# 09_-_Ethernet.net
KiCad netlist of a schematic drawn in Altium Designer
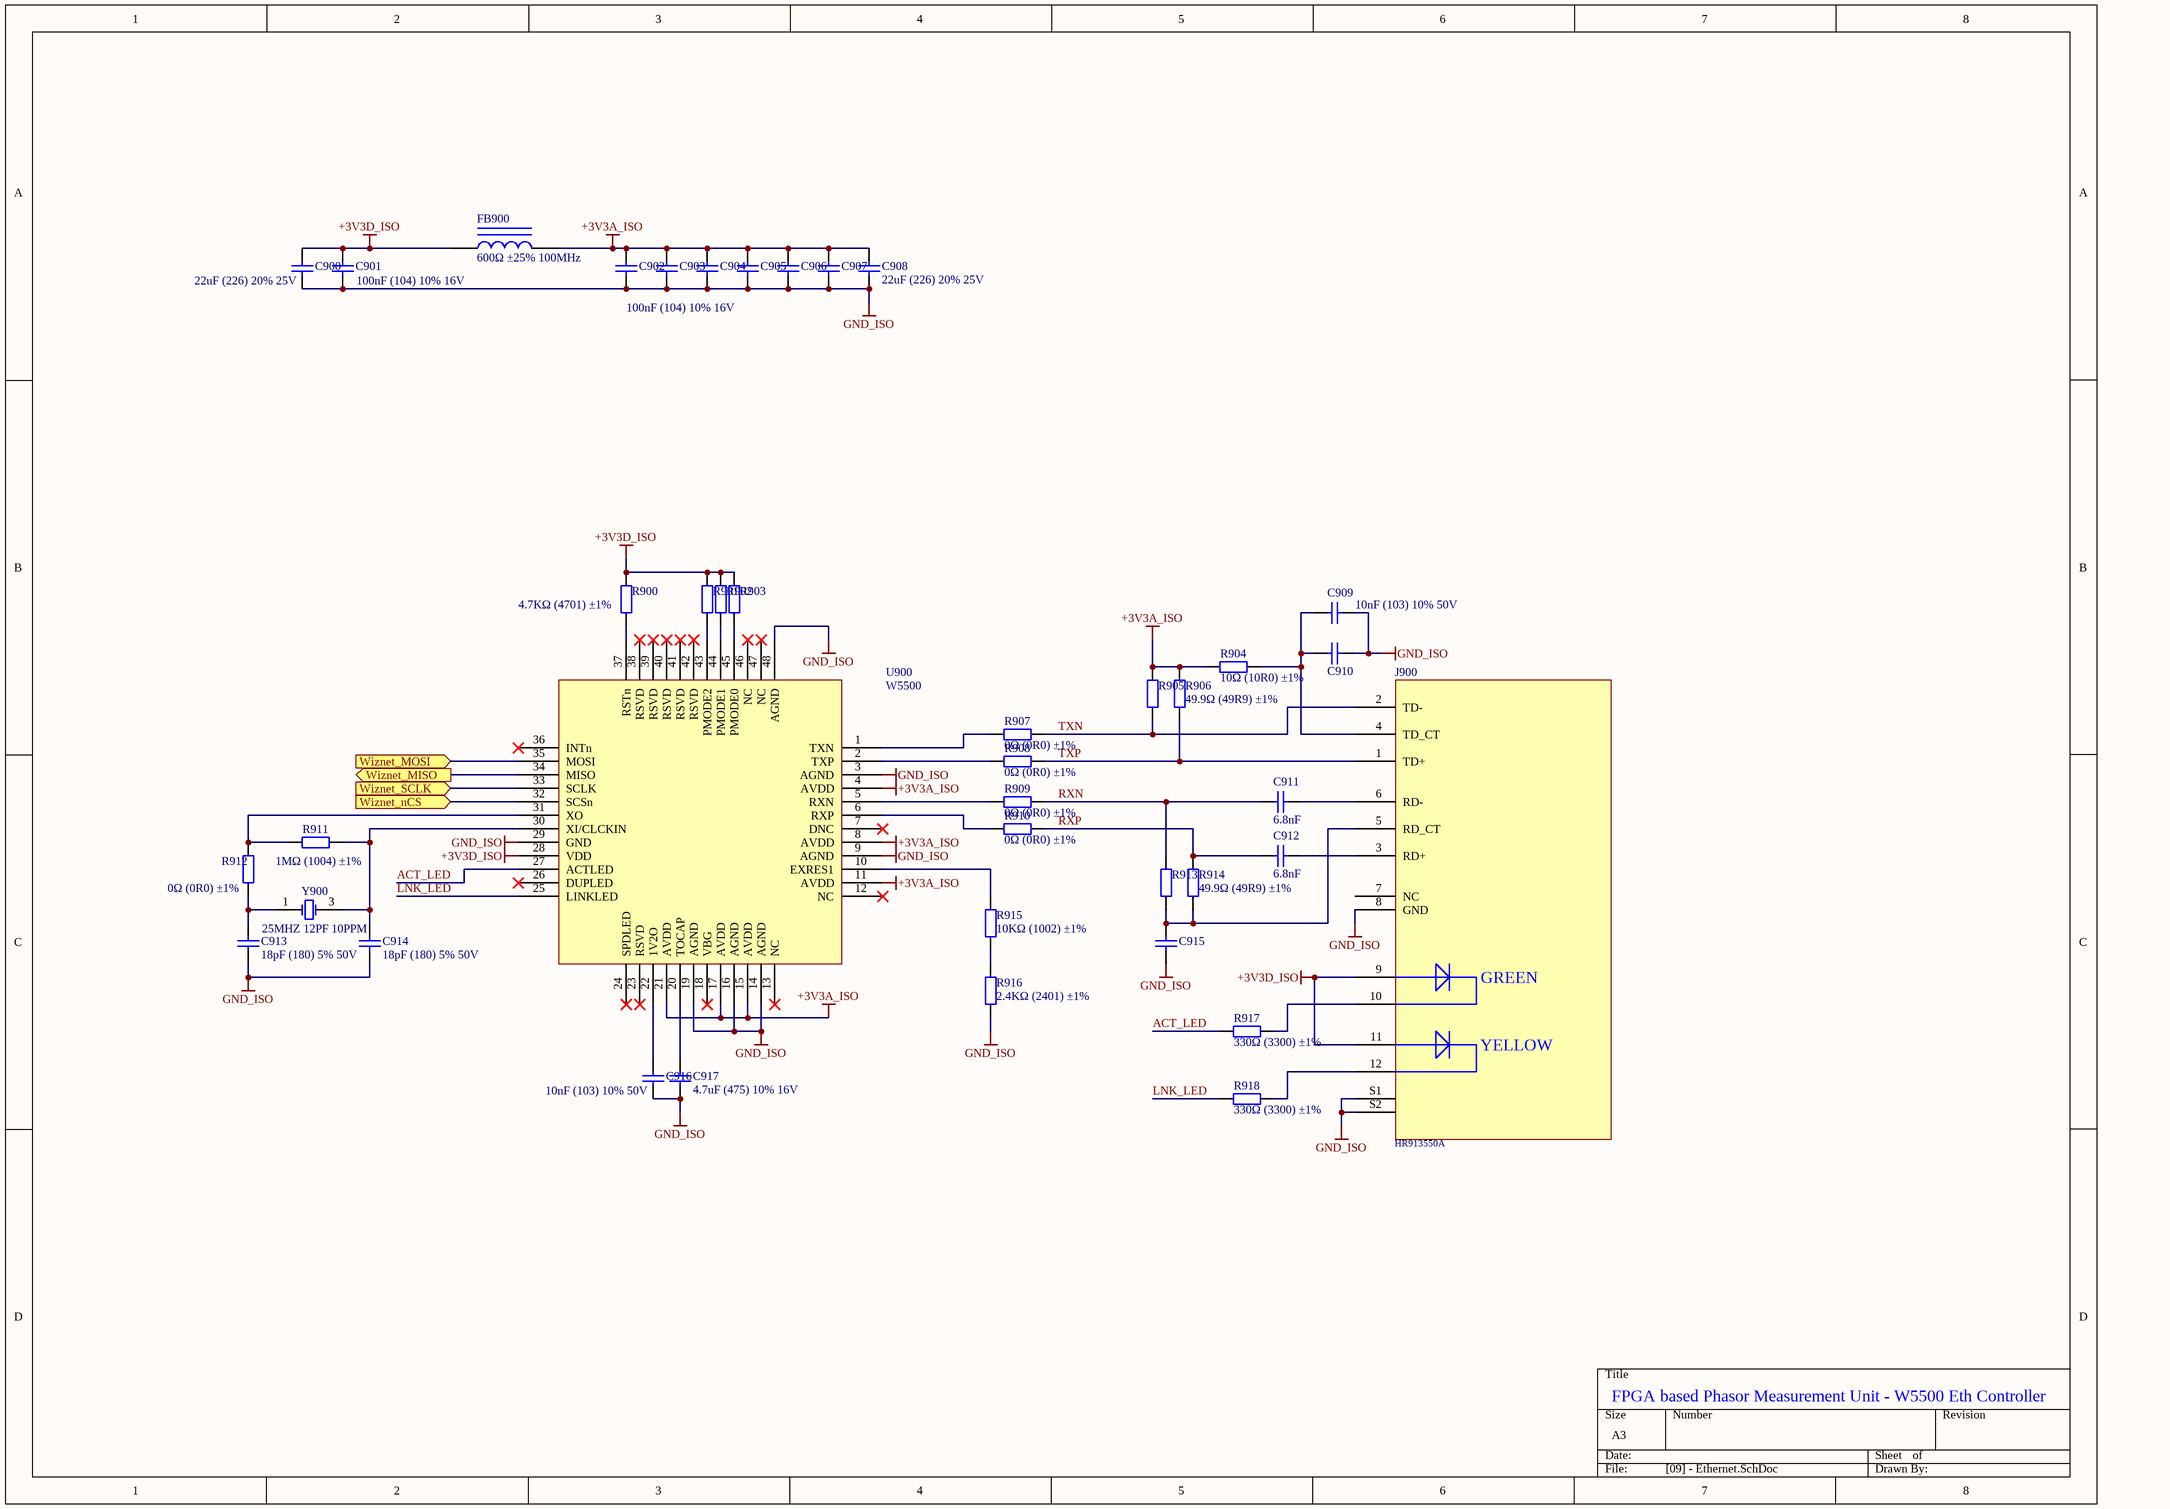
[diagram p0: [09] - Ethernet.SchDoc]

(export (version "E")
  (design (tool "Eeschema 10.0.6"))
  (components
    (comp (ref "C900")
      (value "22uF (226) 20% 25V")
      (footprint "0805_C")
      (description "贴片电容")
      (libsource (lib "Cap") (part "0805 22uF (226) 20% 25V"))
    )
    (comp (ref "C901")
      (value "100nF (104) 10% 16V")
      (footprint "0402_C")
      (description "贴片电容")
      (libsource (lib "Cap") (part "0402 100nF (104) 10% 16V"))
    )
    (comp (ref "C902")
      (value "100nF (104) 10% 16V")
      (footprint "0402_C")
      (description "贴片电容")
      (libsource (lib "Cap") (part "0402 100nF (104) 10% 16V"))
    )
    (comp (ref "C903")
      (value "100nF (104) 10% 16V")
      (footprint "0402_C")
      (description "贴片电容")
      (libsource (lib "Cap") (part "0402 100nF (104) 10% 16V"))
    )
    (comp (ref "C904")
      (value "100nF (104) 10% 16V")
      (footprint "0402_C")
      (description "贴片电容")
      (libsource (lib "Cap") (part "0402 100nF (104) 10% 16V"))
    )
    (comp (ref "C905")
      (value "100nF (104) 10% 16V")
      (footprint "0402_C")
      (description "贴片电容")
      (libsource (lib "Cap") (part "0402 100nF (104) 10% 16V"))
    )
    (comp (ref "C906")
      (value "100nF (104) 10% 16V")
      (footprint "0402_C")
      (description "贴片电容")
      (libsource (lib "Cap") (part "0402 100nF (104) 10% 16V"))
    )
    (comp (ref "C907")
      (value "100nF (104) 10% 16V")
      (footprint "0402_C")
      (description "贴片电容")
      (libsource (lib "Cap") (part "0402 100nF (104) 10% 16V"))
    )
    (comp (ref "C908")
      (value "22uF (226) 20% 25V")
      (footprint "0805_C")
      (description "贴片电容")
      (libsource (lib "Cap") (part "0805 22uF (226) 20% 25V"))
    )
    (comp (ref "C909")
      (value "10nF (103) 10% 50V")
      (footprint "0402_C")
      (description "贴片电容")
      (libsource (lib "Cap") (part "0402 10nF (103) 10% 50V"))
    )
    (comp (ref "C910")
      (value "10nF (103) 10% 50V")
      (footprint "0402_C")
      (description "贴片电容")
      (libsource (lib "Cap") (part "0402 10nF (103) 10% 50V"))
    )
    (comp (ref "C911")
      (value "6.8nF")
      (footprint "0402_C")
      (description "贴片电容")
      (libsource (lib "Cap") (part "0402 6.8nF (682) 10% 50V"))
    )
    (comp (ref "C912")
      (value "6.8nF")
      (footprint "0402_C")
      (description "贴片电容")
      (libsource (lib "Cap") (part "0402 6.8nF (682) 10% 50V"))
    )
    (comp (ref "C913")
      (value "18pF (180) 5% 50V")
      (footprint "0402_C")
      (description "贴片电容")
      (libsource (lib "Cap") (part "0402 18pF (180) 5% 50V"))
    )
    (comp (ref "C914")
      (value "18pF (180) 5% 50V")
      (footprint "0402_C")
      (description "贴片电容")
      (libsource (lib "Cap") (part "0402 18pF (180) 5% 50V"))
    )
    (comp (ref "C915")
      (value "10nF (103) 10% 50V")
      (footprint "0402_C")
      (description "贴片电容")
      (libsource (lib "Cap") (part "0402 10nF (103) 10% 50V"))
    )
    (comp (ref "C916")
      (value "10nF (103) 10% 50V")
      (footprint "0402_C")
      (description "贴片电容")
      (libsource (lib "Cap") (part "0402 10nF (103) 10% 50V"))
    )
    (comp (ref "C917")
      (value "4.7uF (475) 10% 16V")
      (footprint "0603_C")
      (description "贴片电容")
      (libsource (lib "Cap") (part "0603 4.7uF (475) 10% 16V"))
    )
    (comp (ref "FB900")
      (value "600Ω ±25% 100MHz")
      (footprint "0805_L")
      (description "贴片磁珠")
      (libsource (lib "IUD") (part "0805 600Ω 25% 100MHz"))
    )
    (comp (ref "J900")
      (value "HR913550A")
      (footprint "RJ45 MagJack")
      (description "RJ45 12 1 Green - Yellow Through Hole Ethernet Connectors/Modular Connectors (RJ45 RJ11) RoHS")
      (libsource (lib "FPGA_PMU_lib") (part "HR913550A"))
    )
    (comp (ref "R900")
      (value "4.7KΩ (4701) ±1%")
      (footprint "0402_R")
      (description "贴片电阻")
      (libsource (lib "") (part "0402 4.7KΩ (4701) 1%_1"))
    )
    (comp (ref "R901")
      (value "4.7KΩ (4701) ±1%")
      (footprint "0402_R")
      (description "贴片电阻")
      (libsource (lib "RES") (part "0402 4.7KΩ (4701) 1%"))
    )
    (comp (ref "R902")
      (value "4.7KΩ (4701) ±1%")
      (footprint "0402_R")
      (description "贴片电阻")
      (libsource (lib "RES") (part "0402 4.7KΩ (4701) 1%"))
    )
    (comp (ref "R903")
      (value "4.7KΩ (4701) ±1%")
      (footprint "0402_R")
      (description "贴片电阻")
      (libsource (lib "RES") (part "0402 4.7KΩ (4701) 1%"))
    )
    (comp (ref "R904")
      (value "10Ω (10R0) ±1%")
      (footprint "0402_R")
      (description "贴片电阻")
      (libsource (lib "RES") (part "0402 10Ω (10R0) 1%"))
    )
    (comp (ref "R905")
      (value "49.9Ω (49R9) ±1%")
      (footprint "0402_R")
      (description "贴片电阻")
      (libsource (lib "RES") (part "0402 49.9Ω (49R9) 1%"))
    )
    (comp (ref "R906")
      (value "49.9Ω (49R9) ±1%")
      (footprint "0402_R")
      (description "贴片电阻")
      (libsource (lib "RES") (part "0402 49.9Ω (49R9) 1%"))
    )
    (comp (ref "R907")
      (value "0Ω (0R0) ±1%")
      (footprint "0402_R")
      (description "贴片电阻")
      (libsource (lib "") (part "0402 0Ω (0R0) 1%_1"))
    )
    (comp (ref "R908")
      (value "0Ω (0R0) ±1%")
      (footprint "0402_R")
      (description "贴片电阻")
      (libsource (lib "") (part "0402 0Ω (0R0) 1%_1"))
    )
    (comp (ref "R909")
      (value "0Ω (0R0) ±1%")
      (footprint "0402_R")
      (description "贴片电阻")
      (libsource (lib "") (part "0402 0Ω (0R0) 1%_1"))
    )
    (comp (ref "R910")
      (value "0Ω (0R0) ±1%")
      (footprint "0402_R")
      (description "贴片电阻")
      (libsource (lib "") (part "0402 0Ω (0R0) 1%_1"))
    )
    (comp (ref "R911")
      (value "1MΩ (1004) ±1%")
      (footprint "0402_R")
      (description "贴片电阻")
      (libsource (lib "RES") (part "0402 1MΩ (1004) 1%"))
    )
    (comp (ref "R912")
      (value "0Ω (0R0) ±1%")
      (footprint "0402_R")
      (description "贴片电阻")
      (libsource (lib "RES") (part "0402 0Ω (0R0) 1%"))
    )
    (comp (ref "R913")
      (value "49.9Ω (49R9) ±1%")
      (footprint "0402_R")
      (description "贴片电阻")
      (libsource (lib "RES") (part "0402 49.9Ω (49R9) 1%"))
    )
    (comp (ref "R914")
      (value "49.9Ω (49R9) ±1%")
      (footprint "0402_R")
      (description "贴片电阻")
      (libsource (lib "RES") (part "0402 49.9Ω (49R9) 1%"))
    )
    (comp (ref "R915")
      (value "10KΩ (1002) ±1%")
      (footprint "0402_R")
      (description "贴片电阻")
      (libsource (lib "RES") (part "0402 10KΩ (1002) 1%"))
    )
    (comp (ref "R916")
      (value "2.4KΩ (2401) ±1%")
      (footprint "0402_R")
      (description "贴片电阻")
      (libsource (lib "RES") (part "0402 2.4KΩ (2401) 1%"))
    )
    (comp (ref "R917")
      (value "330Ω (3300) ±1%")
      (footprint "0603_R")
      (description "贴片电阻")
      (libsource (lib "RES") (part "0603 330Ω (3300) 1%"))
    )
    (comp (ref "R918")
      (value "330Ω (3300) ±1%")
      (footprint "0603_R")
      (description "贴片电阻")
      (libsource (lib "RES") (part "0603 330Ω (3300) 1%"))
    )
    (comp (ref "U900")
      (value "W5500")
      (footprint "LQFP-48_7x7x05P")
      (description "以太网")
      (libsource (lib "IC") (part "W5500_[C32843]"))
    )
    (comp (ref "Y900")
      (value "25MHZ 12PF 10PPM")
      (footprint "SMD-3225_4P")
      (description "贴片晶振")
      (libsource (lib "CrystalOscillator") (part "SMD-3225_4P  25MHZ 12PF 10PPM"))
    )
  )
  (nets
    (net (code "1") (name "+3V3A_ISO") (class "Default")
      (node (ref "C902") (pin "2") (pinfunction "2_2") (pintype "passive"))
      (node (ref "C903") (pin "2") (pinfunction "2_2") (pintype "passive"))
      (node (ref "C904") (pin "2") (pinfunction "2_2") (pintype "passive"))
      (node (ref "C905") (pin "2") (pinfunction "2_2") (pintype "passive"))
      (node (ref "C906") (pin "2") (pinfunction "2_2") (pintype "passive"))
      (node (ref "C907") (pin "2") (pinfunction "2_2") (pintype "passive"))
      (node (ref "C908") (pin "2") (pinfunction "2_2") (pintype "passive"))
      (node (ref "FB900") (pin "2") (pinfunction "2_2") (pintype "passive"))
      (node (ref "R904") (pin "1") (pinfunction "1_1") (pintype "passive"))
      (node (ref "R905") (pin "2") (pinfunction "2_2") (pintype "passive"))
      (node (ref "R906") (pin "2") (pinfunction "2_2") (pintype "passive"))
      (node (ref "U900") (pin "11") (pinfunction "AVDD_11") (pintype "passive"))
      (node (ref "U900") (pin "15") (pinfunction "AVDD_15") (pintype "passive"))
      (node (ref "U900") (pin "17") (pinfunction "AVDD_17") (pintype "passive"))
      (node (ref "U900") (pin "21") (pinfunction "AVDD_21") (pintype "passive"))
      (node (ref "U900") (pin "4") (pinfunction "AVDD_4") (pintype "passive"))
      (node (ref "U900") (pin "8") (pinfunction "AVDD_8") (pintype "passive"))
    )
    (net (code "2") (name "+3V3D_ISO") (class "Default")
      (node (ref "C900") (pin "2") (pinfunction "2_2") (pintype "passive"))
      (node (ref "C901") (pin "2") (pinfunction "2_2") (pintype "passive"))
      (node (ref "FB900") (pin "1") (pinfunction "1_1") (pintype "passive"))
      (node (ref "J900") (pin "11") (pinfunction "11_11") (pintype "passive"))
      (node (ref "J900") (pin "9") (pinfunction "9_9") (pintype "passive"))
      (node (ref "R900") (pin "1") (pinfunction "1_1") (pintype "passive"))
      (node (ref "R901") (pin "2") (pinfunction "2_2") (pintype "passive"))
      (node (ref "R902") (pin "2") (pinfunction "2_2") (pintype "passive"))
      (node (ref "R903") (pin "2") (pinfunction "2_2") (pintype "passive"))
      (node (ref "U900") (pin "28") (pinfunction "VDD_28") (pintype "passive"))
    )
    (net (code "3") (name "/ACT_LED") (class "Default")
      (node (ref "R917") (pin "1") (pinfunction "1_1") (pintype "passive"))
      (node (ref "U900") (pin "27") (pinfunction "ACTLED_27") (pintype "passive"))
    )
    (net (code "4") (name "/LNK_LED") (class "Default")
      (node (ref "R918") (pin "1") (pinfunction "1_1") (pintype "passive"))
      (node (ref "U900") (pin "25") (pinfunction "LINKLED_25") (pintype "passive"))
    )
    (net (code "5") (name "/RXN") (class "Default")
      (node (ref "C911") (pin "1") (pinfunction "1_1") (pintype "passive"))
      (node (ref "R909") (pin "2") (pinfunction "2_2") (pintype "passive"))
      (node (ref "R913") (pin "2") (pinfunction "2_2") (pintype "passive"))
    )
    (net (code "6") (name "/RXP") (class "Default")
      (node (ref "C912") (pin "1") (pinfunction "1_1") (pintype "passive"))
      (node (ref "R910") (pin "2") (pinfunction "2_2") (pintype "passive"))
      (node (ref "R914") (pin "2") (pinfunction "2_2") (pintype "passive"))
    )
    (net (code "7") (name "/TXN") (class "Default")
      (node (ref "J900") (pin "2") (pinfunction "TD-_2") (pintype "passive"))
      (node (ref "R905") (pin "1") (pinfunction "1_1") (pintype "passive"))
      (node (ref "R907") (pin "2") (pinfunction "2_2") (pintype "passive"))
    )
    (net (code "8") (name "/TXP") (class "Default")
      (node (ref "J900") (pin "1") (pinfunction "TD+_1") (pintype "passive"))
      (node (ref "R906") (pin "1") (pinfunction "1_1") (pintype "passive"))
      (node (ref "R908") (pin "2") (pinfunction "2_2") (pintype "passive"))
    )
    (net (code "9") (name "/Wiznet_MISO") (class "Default")
      (node (ref "U900") (pin "34") (pinfunction "MISO_34") (pintype "passive"))
    )
    (net (code "10") (name "/Wiznet_MOSI") (class "Default")
      (node (ref "U900") (pin "35") (pinfunction "MOSI_35") (pintype "passive"))
    )
    (net (code "11") (name "/Wiznet_SCLK") (class "Default")
      (node (ref "U900") (pin "33") (pinfunction "SCLK_33") (pintype "passive"))
    )
    (net (code "12") (name "/Wiznet_nCS") (class "Default")
      (node (ref "U900") (pin "32") (pinfunction "SCSn_32") (pintype "passive"))
    )
    (net (code "13") (name "GND_ISO") (class "Default")
      (node (ref "C900") (pin "1") (pinfunction "1_1") (pintype "passive"))
      (node (ref "C901") (pin "1") (pinfunction "1_1") (pintype "passive"))
      (node (ref "C902") (pin "1") (pinfunction "1_1") (pintype "passive"))
      (node (ref "C903") (pin "1") (pinfunction "1_1") (pintype "passive"))
      (node (ref "C904") (pin "1") (pinfunction "1_1") (pintype "passive"))
      (node (ref "C905") (pin "1") (pinfunction "1_1") (pintype "passive"))
      (node (ref "C906") (pin "1") (pinfunction "1_1") (pintype "passive"))
      (node (ref "C907") (pin "1") (pinfunction "1_1") (pintype "passive"))
      (node (ref "C908") (pin "1") (pinfunction "1_1") (pintype "passive"))
      (node (ref "C909") (pin "1") (pinfunction "1_1") (pintype "passive"))
      (node (ref "C910") (pin "1") (pinfunction "1_1") (pintype "passive"))
      (node (ref "C913") (pin "1") (pinfunction "1_1") (pintype "passive"))
      (node (ref "C914") (pin "1") (pinfunction "1_1") (pintype "passive"))
      (node (ref "C915") (pin "1") (pinfunction "1_1") (pintype "passive"))
      (node (ref "C916") (pin "1") (pinfunction "1_1") (pintype "passive"))
      (node (ref "C917") (pin "1") (pinfunction "1_1") (pintype "passive"))
      (node (ref "J900") (pin "8") (pinfunction "GND_8") (pintype "passive"))
      (node (ref "J900") (pin "S1") (pinfunction "S1_S1") (pintype "passive"))
      (node (ref "J900") (pin "S2") (pinfunction "S2_S2") (pintype "passive"))
      (node (ref "R916") (pin "1") (pinfunction "1_1") (pintype "passive"))
      (node (ref "U900") (pin "14") (pinfunction "AGND_14") (pintype "passive"))
      (node (ref "U900") (pin "16") (pinfunction "AGND_16") (pintype "passive"))
      (node (ref "U900") (pin "19") (pinfunction "AGND_19") (pintype "passive"))
      (node (ref "U900") (pin "29") (pinfunction "GND_29") (pintype "passive"))
      (node (ref "U900") (pin "3") (pinfunction "AGND_3") (pintype "passive"))
      (node (ref "U900") (pin "48") (pinfunction "AGND_48") (pintype "passive"))
      (node (ref "U900") (pin "9") (pinfunction "AGND_9") (pintype "passive"))
    )
    (net (code "14") (name "Net-(J900-Pad10)") (class "Default")
      (node (ref "J900") (pin "10") (pinfunction "10_10") (pintype "passive"))
      (node (ref "R917") (pin "2") (pinfunction "2_2") (pintype "passive"))
    )
    (net (code "15") (name "Net-(J900-Pad12)") (class "Default")
      (node (ref "J900") (pin "12") (pinfunction "12_12") (pintype "passive"))
      (node (ref "R918") (pin "2") (pinfunction "2_2") (pintype "passive"))
    )
    (net (code "16") (name "Net-(J900-RD+)") (class "Default")
      (node (ref "C912") (pin "2") (pinfunction "2_2") (pintype "passive"))
      (node (ref "J900") (pin "3") (pinfunction "RD+_3") (pintype "passive"))
    )
    (net (code "17") (name "Net-(J900-RD-)") (class "Default")
      (node (ref "C911") (pin "2") (pinfunction "2_2") (pintype "passive"))
      (node (ref "J900") (pin "6") (pinfunction "RD-_6") (pintype "passive"))
    )
    (net (code "18") (name "Net-(J900-RD_CT)") (class "Default")
      (node (ref "C915") (pin "2") (pinfunction "2_2") (pintype "passive"))
      (node (ref "J900") (pin "5") (pinfunction "RD_CT_5") (pintype "passive"))
      (node (ref "R913") (pin "1") (pinfunction "1_1") (pintype "passive"))
      (node (ref "R914") (pin "1") (pinfunction "1_1") (pintype "passive"))
    )
    (net (code "19") (name "Net-(J900-TD_CT)") (class "Default")
      (node (ref "C909") (pin "2") (pinfunction "2_2") (pintype "passive"))
      (node (ref "C910") (pin "2") (pinfunction "2_2") (pintype "passive"))
      (node (ref "J900") (pin "4") (pinfunction "TD_CT_4") (pintype "passive"))
      (node (ref "R904") (pin "2") (pinfunction "2_2") (pintype "passive"))
    )
    (net (code "20") (name "Net-(R915-Pad1)") (class "Default")
      (node (ref "R915") (pin "1") (pinfunction "1_1") (pintype "passive"))
      (node (ref "R916") (pin "2") (pinfunction "2_2") (pintype "passive"))
    )
    (net (code "21") (name "Net-(U900-1V2O)") (class "Default")
      (node (ref "C916") (pin "2") (pinfunction "2_2") (pintype "passive"))
      (node (ref "U900") (pin "22") (pinfunction "1V2O_22") (pintype "passive"))
    )
    (net (code "22") (name "Net-(U900-EXRES1)") (class "Default")
      (node (ref "R915") (pin "2") (pinfunction "2_2") (pintype "passive"))
      (node (ref "U900") (pin "10") (pinfunction "EXRES1_10") (pintype "passive"))
    )
    (net (code "23") (name "Net-(U900-PMODE0)") (class "Default")
      (node (ref "R903") (pin "1") (pinfunction "1_1") (pintype "passive"))
      (node (ref "U900") (pin "45") (pinfunction "PMODE0_45") (pintype "passive"))
    )
    (net (code "24") (name "Net-(U900-PMODE1)") (class "Default")
      (node (ref "R902") (pin "1") (pinfunction "1_1") (pintype "passive"))
      (node (ref "U900") (pin "44") (pinfunction "PMODE1_44") (pintype "passive"))
    )
    (net (code "25") (name "Net-(U900-PMODE2)") (class "Default")
      (node (ref "R901") (pin "1") (pinfunction "1_1") (pintype "passive"))
      (node (ref "U900") (pin "43") (pinfunction "PMODE2_43") (pintype "passive"))
    )
    (net (code "26") (name "Net-(U900-RSTn)") (class "Default")
      (node (ref "R900") (pin "2") (pinfunction "2_2") (pintype "passive"))
      (node (ref "U900") (pin "37") (pinfunction "RSTn_37") (pintype "passive"))
    )
    (net (code "27") (name "Net-(U900-RXN)") (class "Default")
      (node (ref "R909") (pin "1") (pinfunction "1_1") (pintype "passive"))
      (node (ref "U900") (pin "5") (pinfunction "RXN_5") (pintype "passive"))
    )
    (net (code "28") (name "Net-(U900-RXP)") (class "Default")
      (node (ref "R910") (pin "1") (pinfunction "1_1") (pintype "passive"))
      (node (ref "U900") (pin "6") (pinfunction "RXP_6") (pintype "passive"))
    )
    (net (code "29") (name "Net-(U900-TOCAP)") (class "Default")
      (node (ref "C917") (pin "2") (pinfunction "2_2") (pintype "passive"))
      (node (ref "U900") (pin "20") (pinfunction "TOCAP_20") (pintype "passive"))
    )
    (net (code "30") (name "Net-(U900-TXN)") (class "Default")
      (node (ref "R907") (pin "1") (pinfunction "1_1") (pintype "passive"))
      (node (ref "U900") (pin "1") (pinfunction "TXN_1") (pintype "passive"))
    )
    (net (code "31") (name "Net-(U900-TXP)") (class "Default")
      (node (ref "R908") (pin "1") (pinfunction "1_1") (pintype "passive"))
      (node (ref "U900") (pin "2") (pinfunction "TXP_2") (pintype "passive"))
    )
    (net (code "32") (name "Net-(U900-XI{slash}CLCKIN)") (class "Default")
      (node (ref "C914") (pin "2") (pinfunction "2_2") (pintype "passive"))
      (node (ref "R911") (pin "2") (pinfunction "2_2") (pintype "passive"))
      (node (ref "U900") (pin "30") (pinfunction "XI/CLCKIN_30") (pintype "passive"))
      (node (ref "Y900") (pin "3") (pinfunction "OSC2_3") (pintype "passive"))
    )
    (net (code "33") (name "Net-(U900-XO)") (class "Default")
      (node (ref "R911") (pin "1") (pinfunction "1_1") (pintype "passive"))
      (node (ref "R912") (pin "2") (pinfunction "2_2") (pintype "passive"))
      (node (ref "U900") (pin "31") (pinfunction "XO_31") (pintype "passive"))
    )
    (net (code "34") (name "Net-(Y900-OSC1)") (class "Default")
      (node (ref "C913") (pin "2") (pinfunction "2_2") (pintype "passive"))
      (node (ref "R912") (pin "1") (pinfunction "1_1") (pintype "passive"))
      (node (ref "Y900") (pin "1") (pinfunction "OSC1_1") (pintype "passive"))
    )
    (net (code "35") (name "unconnected-(J900-NC-Pad7)") (class "Default")
      (node (ref "J900") (pin "7") (pinfunction "NC_7") (pintype "passive"))
    )
    (net (code "36") (name "unconnected-(U900-DNC-Pad7)") (class "Default")
      (node (ref "U900") (pin "7") (pinfunction "DNC_7") (pintype "passive+no_connect"))
    )
    (net (code "37") (name "unconnected-(U900-DUPLED-Pad26)") (class "Default")
      (node (ref "U900") (pin "26") (pinfunction "DUPLED_26") (pintype "passive+no_connect"))
    )
    (net (code "38") (name "unconnected-(U900-INTn-Pad36)") (class "Default")
      (node (ref "U900") (pin "36") (pinfunction "INTn_36") (pintype "passive+no_connect"))
    )
    (net (code "39") (name "unconnected-(U900-NC-Pad12)") (class "Default")
      (node (ref "U900") (pin "12") (pinfunction "NC_12") (pintype "passive+no_connect"))
    )
    (net (code "40") (name "unconnected-(U900-NC-Pad13)") (class "Default")
      (node (ref "U900") (pin "13") (pinfunction "NC_13") (pintype "passive+no_connect"))
    )
    (net (code "41") (name "unconnected-(U900-NC-Pad46)") (class "Default")
      (node (ref "U900") (pin "46") (pinfunction "NC_46") (pintype "passive+no_connect"))
    )
    (net (code "42") (name "unconnected-(U900-NC-Pad47)") (class "Default")
      (node (ref "U900") (pin "47") (pinfunction "NC_47") (pintype "passive+no_connect"))
    )
    (net (code "43") (name "unconnected-(U900-RSVD-Pad23)") (class "Default")
      (node (ref "U900") (pin "23") (pinfunction "RSVD_23") (pintype "passive+no_connect"))
    )
    (net (code "44") (name "unconnected-(U900-RSVD-Pad38)") (class "Default")
      (node (ref "U900") (pin "38") (pinfunction "RSVD_38") (pintype "passive+no_connect"))
    )
    (net (code "45") (name "unconnected-(U900-RSVD-Pad39)") (class "Default")
      (node (ref "U900") (pin "39") (pinfunction "RSVD_39") (pintype "passive+no_connect"))
    )
    (net (code "46") (name "unconnected-(U900-RSVD-Pad40)") (class "Default")
      (node (ref "U900") (pin "40") (pinfunction "RSVD_40") (pintype "passive+no_connect"))
    )
    (net (code "47") (name "unconnected-(U900-RSVD-Pad41)") (class "Default")
      (node (ref "U900") (pin "41") (pinfunction "RSVD_41") (pintype "passive+no_connect"))
    )
    (net (code "48") (name "unconnected-(U900-RSVD-Pad42)") (class "Default")
      (node (ref "U900") (pin "42") (pinfunction "RSVD_42") (pintype "passive+no_connect"))
    )
    (net (code "49") (name "unconnected-(U900-SPDLED-Pad24)") (class "Default")
      (node (ref "U900") (pin "24") (pinfunction "SPDLED_24") (pintype "passive+no_connect"))
    )
    (net (code "50") (name "unconnected-(U900-VBG-Pad18)") (class "Default")
      (node (ref "U900") (pin "18") (pinfunction "VBG_18") (pintype "passive+no_connect"))
    )
  )
)
